# 3V3_LDO.net
KiCad netlist of a schematic drawn in Altium Designer
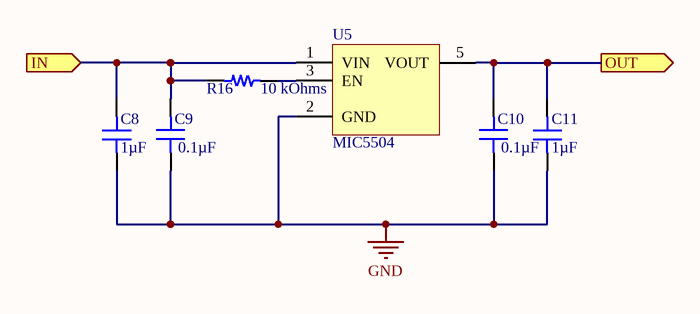
[diagram p0: 3V3_LDO.SchDoc]

(export (version "E")
  (design (tool "Eeschema 10.0.6"))
  (components
    (comp (ref "C8")
      (value "1µF")
      (footprint "CAP 0603_1608")
      (description "CAP CER 1UF 25V X7R 0603")
      (fields
        (field (name "PART NUMBER") "GCJ188R71E105KA01D")
        (field (name "MANUFACTURER") "Murata Electronics")
      )
      (libsource (lib "Celestial Altium Library - altium_library") (part "Capacitor"))
    )
    (comp (ref "C9")
      (value "0.1µF")
      (footprint "CAP 0603_1608")
      (description "CAP CER 0.1UF 100V 0603 EPOXY")
      (fields
        (field (name "PART NUMBER") "GCG188R92A104KA03D")
        (field (name "MANUFACTURER") "Murata Electronics")
      )
      (libsource (lib "Celestial Altium Library - altium_library") (part "Capacitor"))
    )
    (comp (ref "C10")
      (value "0.1µF")
      (footprint "CAP 0603_1608")
      (description "CAP CER 0.1UF 100V 0603 EPOXY")
      (fields
        (field (name "PART NUMBER") "GCG188R92A104KA03D")
        (field (name "MANUFACTURER") "Murata Electronics")
      )
      (libsource (lib "Celestial Altium Library - altium_library") (part "Capacitor"))
    )
    (comp (ref "C11")
      (value "1µF")
      (footprint "CAP 0603_1608")
      (description "CAP CER 1UF 25V X7R 0603")
      (fields
        (field (name "PART NUMBER") "GCJ188R71E105KA01D")
        (field (name "MANUFACTURER") "Murata Electronics")
      )
      (libsource (lib "Celestial Altium Library - altium_library") (part "Capacitor"))
    )
    (comp (ref "R16")
      (value "10 kOhms")
      (footprint "RES 0603_1608")
      (description "RES 10K OHM 0.1% 1/16W 0603")
      (fields
        (field (name "PART NUMBER") "RNCS0603BKE10K0")
        (field (name "MANUFACTURER") "Stackpole Electronics Inc")
      )
      (libsource (lib "Celestial Altium Library - altium_library") (part "Resistor"))
    )
    (comp (ref "U5")
      (value "MIC5504")
      (footprint "TI SOT-23-5 DBV")
      (description "3.3V LDO")
      (libsource (lib "IC") (part "MIC5504-3.3YM5"))
    )
  )
  (nets
    (net (code "1") (name "/IN") (class "Default")
      (node (ref "C8") (pin "2") (pinfunction "2_2") (pintype "passive"))
      (node (ref "C9") (pin "1") (pinfunction "1_1") (pintype "passive"))
      (node (ref "R16") (pin "2") (pinfunction "2_2") (pintype "passive"))
      (node (ref "U5") (pin "1") (pinfunction "VIN_1") (pintype "passive"))
    )
    (net (code "2") (name "/OUT") (class "Default")
      (node (ref "C10") (pin "1") (pinfunction "1_1") (pintype "passive"))
      (node (ref "C11") (pin "2") (pinfunction "2_2") (pintype "passive"))
      (node (ref "U5") (pin "5") (pinfunction "VOUT_5") (pintype "passive"))
    )
    (net (code "3") (name "GND") (class "Default")
      (node (ref "C10") (pin "2") (pinfunction "2_2") (pintype "passive"))
      (node (ref "C11") (pin "1") (pinfunction "1_1") (pintype "passive"))
      (node (ref "C8") (pin "1") (pinfunction "1_1") (pintype "passive"))
      (node (ref "C9") (pin "2") (pinfunction "2_2") (pintype "passive"))
      (node (ref "U5") (pin "2") (pinfunction "GND_2") (pintype "passive"))
    )
    (net (code "4") (name "Net-(U5-EN)") (class "Default")
      (node (ref "R16") (pin "1") (pinfunction "1_1") (pintype "passive"))
      (node (ref "U5") (pin "3") (pinfunction "EN_3") (pintype "passive"))
    )
  )
)
